# IGBT2020.net
KiCad netlist of a schematic drawn in Altium Designer
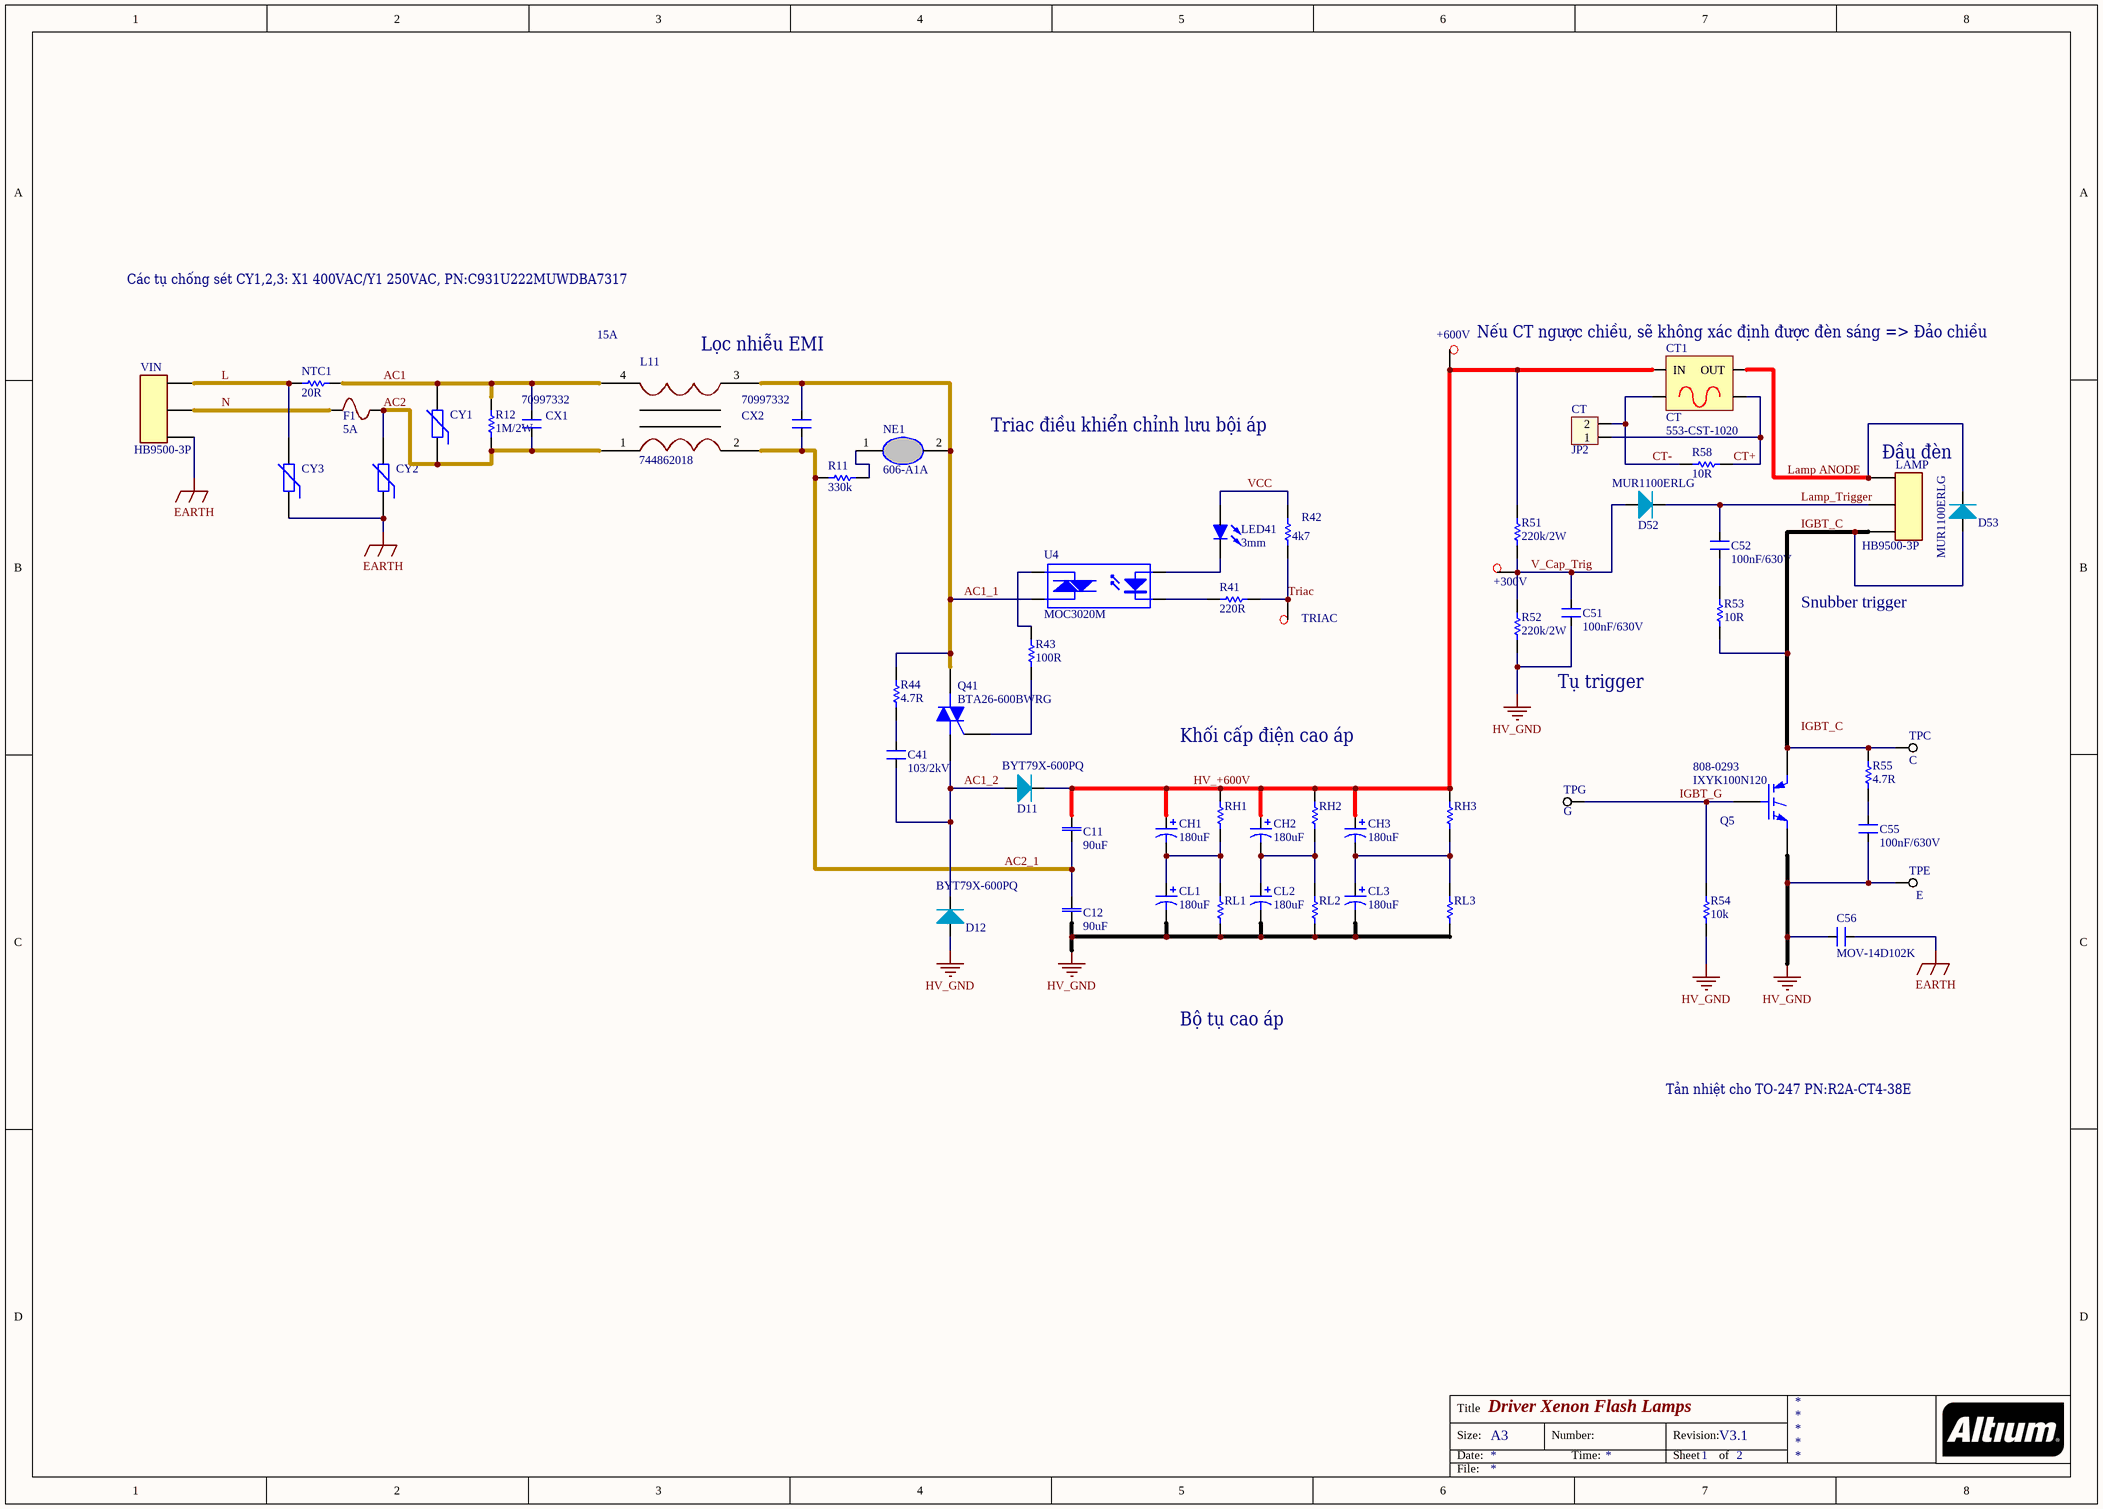
[diagram p0: IGBT2020.SchDoc]

(export (version "E")
  (design (tool "Eeschema 10.0.6"))
  (components
    (comp (ref "+300V") (value "TP") (footprint "swatpcblib:TP2") (libsource (lib "swatpcblib") (part "TP")))
    (comp (ref "+600V") (value "TP") (footprint "swatpcblib:TP2") (libsource (lib "swatpcblib") (part "TP")))
    (comp (ref "C11")
      (value "C4AQ, Film, Metallized Polypropylene, Automotive DC Link, 90 uF, 10%, 500 V, 70C, Lead Spacing = 37.5mm")
      (footprint "PCBLibrary:Kemet 90uF 500V")
      (fields
        (field (name "MANUFACTURER") "WIMA")
        (field (name "MANUFACTURER PART NUMBER") "C4AQLBW5900A3OK")
        (field (name "CAPACITANCE") "90uF")
        (field (name "TOLERANCE") "10%")
      )
      (libsource (lib "swatpcblib") (part "CAP NP"))
    )
    (comp (ref "C12")
      (value "C4AQ, Film, Metallized Polypropylene, Automotive DC Link, 90 uF, 10%, 500 V, 70C, Lead Spacing = 37.5mm")
      (footprint "PCBLibrary:Kemet 90uF 500V")
      (fields
        (field (name "MANUFACTURER") "WIMA")
        (field (name "MANUFACTURER PART NUMBER") "C4AQLBW5900A3OK")
        (field (name "CAPACITANCE") "90uF")
        (field (name "TOLERANCE") "10%")
      )
      (libsource (lib "swatpcblib") (part "CAP NP"))
    )
    (comp (ref "C41")
      (value "103/2kV")
      (footprint "CN2-LT")
      (description "Tụ cao áp chân cắm")
      (libsource (lib "Schematic Library") (part "CN"))
    )
    (comp (ref "C51")
      (value "100nF/630V")
      (footprint "X2 CAP")
      (fields
        (field (name "MANUFACTURER") "TDK EPCOS")
        (field (name "MANUFACTURER PART NUMBER") "B32652-A6104-J")
        (field (name "TOLERANCE") "5%")
      )
      (libsource (lib "Schematic Library") (part "CN"))
    )
    (comp (ref "C52")
      (value "100nF/630V")
      (footprint "X2 CAP")
      (fields
        (field (name "MANUFACTURER") "TDK EPCOS")
        (field (name "MANUFACTURER PART NUMBER") "B32652-A6104-J")
        (field (name "TOLERANCE") "5%")
      )
      (libsource (lib "Schematic Library") (part "CN"))
    )
    (comp (ref "C55")
      (value "100nF/630V")
      (footprint "X2 CAP")
      (fields
        (field (name "MANUFACTURER") "TDK EPCOS")
        (field (name "MANUFACTURER PART NUMBER") "B32652-A6104-J")
        (field (name "TOLERANCE") "5%")
      )
      (libsource (lib "Schematic Library") (part "CN"))
    )
    (comp (ref "C56")
      (value "MOV-14D102K")
      (footprint "MOV")
      (description "Tụ cao áp chân cắm")
      (fields (field (name "MANUFACTURER") "Bourns") (field (name "TOLERANCE") "10%"))
      (libsource (lib "Schematic Library") (part "CN"))
    )
    (comp (ref "CH1")
      (value "180uF")
      (footprint "CAP 25x50")
      (fields
        (field (name "MANUFACTURER") "Wurth Electronics")
        (field (name "MANUFACTURER PART NUMBER") "861141483005")
        (field (name "TOLERANCE") "20%")
      )
      (libsource (lib "Schematic Library") (part "CP"))
    )
    (comp (ref "CH2")
      (value "180uF")
      (footprint "CAP 25x50")
      (fields
        (field (name "MANUFACTURER") "Wurth Electronics")
        (field (name "MANUFACTURER PART NUMBER") "861141483005")
        (field (name "TOLERANCE") "20%")
      )
      (libsource (lib "Schematic Library") (part "CP"))
    )
    (comp (ref "CH3")
      (value "180uF")
      (footprint "CAP 25x50")
      (fields
        (field (name "MANUFACTURER") "Wurth Electronics")
        (field (name "MANUFACTURER PART NUMBER") "861141483005")
        (field (name "TOLERANCE") "20%")
      )
      (libsource (lib "Schematic Library") (part "CP"))
    )
    (comp (ref "CL1")
      (value "180uF")
      (footprint "CAP 25x50")
      (fields
        (field (name "MANUFACTURER") "Wurth Electronics")
        (field (name "MANUFACTURER PART NUMBER") "861141483005")
        (field (name "TOLERANCE") "20%")
      )
      (libsource (lib "Schematic Library") (part "CP"))
    )
    (comp (ref "CL2")
      (value "180uF")
      (footprint "CAP 25x50")
      (fields
        (field (name "MANUFACTURER") "Wurth Electronics")
        (field (name "MANUFACTURER PART NUMBER") "861141483005")
        (field (name "TOLERANCE") "20%")
      )
      (libsource (lib "Schematic Library") (part "CP"))
    )
    (comp (ref "CL3")
      (value "180uF")
      (footprint "CAP 25x50")
      (fields
        (field (name "MANUFACTURER") "Wurth Electronics")
        (field (name "MANUFACTURER PART NUMBER") "861141483005")
        (field (name "TOLERANCE") "20%")
      )
      (libsource (lib "Schematic Library") (part "CP"))
    )
    (comp (ref "CT")
      (value "JP2")
      (footprint "heromap:CON2")
      (description "Connector 2")
      (libsource (lib "heromap") (part "Con2"))
    )
    (comp (ref "CT1")
      (value "CT")
      (footprint "PCBComponent_1")
      (description "Biến dòng cách ly 20A/20mA")
      (fields
        (field (name "SUPPLIER PART NUMBER 1") "553-CST-1020")
        (field (name "MANUFACTURER") "Triad Magnetics")
        (field (name "MANUFACTURER PART NUMBER") "CST-1020")
      )
      (libsource (lib "Tuan") (part "CT"))
    )
    (comp (ref "CX1")
      (value "Tụ lọc nhiễu X2 chân cắm220nF70997332")
      (footprint "X2 CAP")
      (description "Tụ lọc nhiễu X2 chân cắm")
      (fields
        (field (name "SPN1") "70997332")
        (field (name "MANUFACTURER") "Wurth Electronics")
        (field (name "MANUFACTURER PART NUMBER") "890324024002CS")
      )
      (libsource (lib "Schematic Library") (part "CN"))
    )
    (comp (ref "CX2")
      (value "Tụ lọc nhiễu X2 chân cắm220nF70997332")
      (footprint "X2 CAP")
      (description "Tụ lọc nhiễu X2 chân cắm")
      (fields
        (field (name "SPN1") "70997332")
        (field (name "MANUFACTURER") "Wurth Electronics")
        (field (name "MANUFACTURER PART NUMBER") "890324024002CS")
      )
      (libsource (lib "Schematic Library") (part "CN"))
    )
    (comp (ref "CY1")
      (value "Varistor chân cắmC931U222MUWDBA7317")
      (footprint "MOV")
      (description "Ceramic Disc Capacitors 250volts 2200pF 20% Y5U")
      (fields (field (name "MANUFACTURER") "KEMET") (field (name "MPN") "C931U222MUWDBA7317"))
      (libsource (lib "Schematic Library") (part "Varistor"))
    )
    (comp (ref "CY2")
      (value "Varistor chân cắmC931U222MUWDBA7317")
      (footprint "MOV")
      (description "Ceramic Disc Capacitors 250volts 2200pF 20% Y5U")
      (fields (field (name "MANUFACTURER") "KEMET") (field (name "MPN") "C931U222MUWDBA7317"))
      (libsource (lib "Schematic Library") (part "Varistor"))
    )
    (comp (ref "CY3")
      (value "Varistor chân cắmC931U222MUWDBA7317")
      (footprint "MOV")
      (description "Ceramic Disc Capacitors 250volts 2200pF 20% Y5U")
      (fields (field (name "MANUFACTURER") "KEMET") (field (name "MPN") "C931U222MUWDBA7317"))
      (libsource (lib "Schematic Library") (part "Varistor"))
    )
    (comp (ref "D11")
      (value "Đi ốt cắmBYT79X-600PQ")
      (footprint "swatpcblib:TO-220F")
      (fields
        (field (name "SUPPLIER PART NUMBER 1") "BYT79X-600PQ")
        (field (name "MANUFACTURER") "WeEn Semiconductors")
        (field (name "MPN") "BYT79X-600PQ")
      )
      (libsource (lib "swatpcblib") (part "Diode"))
    )
    (comp (ref "D12")
      (value "Đi ốt cắmBYT79X-600PQ")
      (footprint "swatpcblib:TO-220F")
      (fields
        (field (name "SUPPLIER PART NUMBER 1") "BYT79X-600PQ")
        (field (name "MANUFACTURER") "WeEn Semiconductors")
        (field (name "MPN") "BYT79X-600PQ")
      )
      (libsource (lib "swatpcblib") (part "Diode"))
    )
    (comp (ref "D52")
      (value "Đi ốt cắmMUR1100ERLG")
      (footprint "swatpcblib:DO-41")
      (description "DIODE GEN PURP 1KV 1A AXIAL")
      (fields (field (name "MANUFACTURER") "ON Semiconductor") (field (name "VL1") "MUR1100ERLG"))
      (libsource (lib "swatpcblib") (part "Diode"))
    )
    (comp (ref "D53")
      (value "Đi ốt cắmMUR1100ERLG")
      (footprint "swatpcblib:DO-41")
      (description "DIODE GEN PURP 1KV 1A AXIAL")
      (fields (field (name "MANUFACTURER") "ON Semiconductor") (field (name "VL1") "MUR1100ERLG"))
      (libsource (lib "swatpcblib") (part "Diode"))
    )
    (comp (ref "F1")
      (value "5A")
      (footprint "Fuse")
      (description "Cầu chì ống thủy tinh")
      (fields (field (name "Comment") "Cầu chì ống thủy tinh5A"))
      (libsource (lib "Schematic Library") (part "Fuse"))
    )
    (comp (ref "L11")
      (value "744862018")
      (footprint "swatpcblib:Choke 5A")
      (description "Cuộn cảm lọc nguồn đầu vào")
      (fields
        (field (name "MANUFACTURER") "Wurth Electronics")
        (field (name "TOLERANCE") "50%")
        (field (name "MAX CURRENT RATING") "15A")
      )
      (libsource (lib "Schematic Library") (part "Choke"))
    )
    (comp (ref "LAMP")
      (value "HB9500-3P")
      (footprint "HB9500-3P")
      (description "Pitch：9.5mm；Poles：3P；Rated Voltage/Current：300V/25A")
      (fields (field (name "Comment") "Giắc nguồn 3 chân. 9.5mm :HB9500-3P"))
      (libsource (lib "") (part "HEADER 3_1"))
    )
    (comp (ref "LED41")
      (value "3mm")
      (footprint "LED 3mm")
      (description "Led vàng chân cắm")
      (libsource (lib "Schematic Library") (part "LED 3mm"))
    )
    (comp (ref "NE1")
      (value "606-A1A")
      (footprint "NE2")
      (description "T2 WIRE TERMINAL NEON (NE-2)")
      (fields (field (name "MANUFACTURER") "VCC CHML") (field (name "MANUFACTURER PART NUMBER") "A1A"))
      (libsource (lib "Schematic Library") (part "NE"))
    )
    (comp (ref "NTC1")
      (value "20R")
      (footprint "PCBLibrary:TO-126")
      (description "NTC")
      (fields
        (field (name "MANUFACTURER") "Bourns")
        (field (name "MANUFACTURER PART NUMBER") "PWR221T-30-R100F")
      )
      (libsource (lib "Schematic Library") (part "Resistor"))
    )
    (comp (ref "Q5")
      (value "IXYK100N120")
      (footprint "TO247+LageHeatsink")
      (description "IGBT 1200V 188A 1150W TO264")
      (fields
        (field (name "SUPPLIER PART NUMBER 1") "808-0293")
        (field (name "MANUFACTURER") "IXYS")
        (field (name "MANUFACTURER PART NUMBER") "IXYK100N120C3")
      )
      (libsource (lib "Schematic Library") (part "IGBT"))
    )
    (comp (ref "Q41")
      (value "BTA26-600BWRG")
      (footprint "TOP3")
      (description "TRIAC, 25A, 600V, TOP-3")
      (fields (field (name "MANUFACTURER") "STMicroelectronics"))
      (libsource (lib "Schematic Library") (part "BTA26-600"))
    )
    (comp (ref "R11")
      (value "330k")
      (footprint "RES-1/4W")
      (description "Trở cắm 1/4W")
      (libsource (lib "Schematic Library") (part "Resistor"))
    )
    (comp (ref "R12")
      (value "1M/2W")
      (footprint "RES-3W")
      (description "Trở cắm 2W")
      (libsource (lib "Schematic Library") (part "Resistor"))
    )
    (comp (ref "R41")
      (value "220R")
      (footprint "RES-SMD-1206")
      (description "Trở dán SMD 1206")
      (libsource (lib "Schematic Library") (part "Resistor"))
    )
    (comp (ref "R42")
      (value "4k7")
      (footprint "RES-SMD-1206")
      (description "Trở dán SMD 1206")
      (libsource (lib "Schematic Library") (part "Resistor"))
    )
    (comp (ref "R43")
      (value "100R")
      (footprint "RES-1W")
      (description "Trở cắm 1W")
      (libsource (lib "Schematic Library") (part "Resistor"))
    )
    (comp (ref "R44")
      (value "4.7R")
      (footprint "heromap:R1/4WD")
      (description "Trở cắm 2W")
      (libsource (lib "Schematic Library") (part "Resistor"))
    )
    (comp (ref "R51")
      (value "220k/2W")
      (footprint "RES-3W")
      (description "Trở cắm 2W")
      (libsource (lib "Schematic Library") (part "Resistor"))
    )
    (comp (ref "R52")
      (value "220k/2W")
      (footprint "RES-3W")
      (description "Trở cắm 2W")
      (libsource (lib "Schematic Library") (part "Resistor"))
    )
    (comp (ref "R53")
      (value "10R")
      (footprint "heromap:R1/4WD")
      (description "Trở cắm 2W")
      (libsource (lib "Schematic Library") (part "Resistor"))
    )
    (comp (ref "R54")
      (value "10k")
      (footprint "PCBLibrary:RES-1/4W")
      (description "Resistor")
      (fields (field (name "Comment") "Điện trở cắm 1/4W10k"))
      (libsource (lib "swatpcblib") (part "Res"))
    )
    (comp (ref "R55")
      (value "4.7R")
      (footprint "heromap:R1/4WD")
      (description "Trở cắm 2W")
      (libsource (lib "Schematic Library") (part "Resistor"))
    )
    (comp (ref "R58")
      (value "10R")
      (footprint "heromap:R1/4WD")
      (description "Trở cắm 2W")
      (libsource (lib "Schematic Library") (part "Resistor"))
    )
    (comp (ref "RH1")
      (value "Trở cắm 1W330k/1W")
      (footprint "RES-1W")
      (description "Trở cắm 2W")
      (libsource (lib "Schematic Library") (part "Resistor"))
    )
    (comp (ref "RH2")
      (value "Trở cắm 1W330k/1W")
      (footprint "RES-1W")
      (description "Trở cắm 2W")
      (libsource (lib "Schematic Library") (part "Resistor"))
    )
    (comp (ref "RH3")
      (value "Trở cắm 1W330k/1W")
      (footprint "RES-1W")
      (description "Trở cắm 2W")
      (libsource (lib "Schematic Library") (part "Resistor"))
    )
    (comp (ref "RL1")
      (value "Trở cắm 1W330k/1W")
      (footprint "RES-1W")
      (description "Trở cắm 2W")
      (libsource (lib "Schematic Library") (part "Resistor"))
    )
    (comp (ref "RL2")
      (value "Trở cắm 1W330k/1W")
      (footprint "RES-1W")
      (description "Trở cắm 2W")
      (libsource (lib "Schematic Library") (part "Resistor"))
    )
    (comp (ref "RL3")
      (value "Trở cắm 1W330k/1W")
      (footprint "RES-1W")
      (description "Trở cắm 2W")
      (libsource (lib "Schematic Library") (part "Resistor"))
    )
    (comp (ref "TPC")
      (value "C")
      (footprint "TP")
      (description "Testpoint C")
      (libsource (lib "Schematic Library") (part "Test Point"))
    )
    (comp (ref "TPE")
      (value "E")
      (footprint "TP")
      (description "Testpoint E")
      (libsource (lib "Schematic Library") (part "Test Point"))
    )
    (comp (ref "TPG")
      (value "G")
      (footprint "TP")
      (description "Testpoint G")
      (libsource (lib "Schematic Library") (part "Test Point"))
    )
    (comp (ref "TRIAC") (value "TP") (footprint "swatpcblib:TP2") (libsource (lib "swatpcblib") (part "TP")))
    (comp (ref "U4")
      (value "MOC3020M")
      (footprint "DIP6/W0.3")
      (description "OPTOISOLATOR 4.17KV TRIAC 6DIP")
      (fields
        (field (name "MANUFACTURER") "ON Semiconductor / Fairchild")
        (field (name "MANUFACTURER PART NUMBER") "MOC3020-M")
      )
      (libsource (lib "Schematic Library") (part "MOC"))
    )
    (comp (ref "VIN")
      (value "HB9500-3P")
      (footprint "HB9500-3P")
      (description "Pitch：9.5mm；Poles：3P；Rated Voltage/Current：300V/25A")
      (fields (field (name "Comment") "Giắc nguồn 3 chân. 9.5mm :HB9500-3P"))
      (libsource (lib "Schematic Library") (part "HEADER 3"))
    )
  )
  (nets
    (net (code "1") (name "/AC1") (class "Default")
      (node (ref "CX1") (pin "2") (pinfunction "2_2") (pintype "passive"))
      (node (ref "CY1") (pin "2") (pinfunction "2_2") (pintype "passive"))
      (node (ref "L11") (pin "4") (pinfunction "4_4") (pintype "passive"))
      (node (ref "NTC1") (pin "2") (pinfunction "2_2") (pintype "passive"))
      (node (ref "R12") (pin "2") (pinfunction "2_2") (pintype "passive"))
    )
    (net (code "2") (name "/AC1_1") (class "Default")
      (node (ref "CX2") (pin "2") (pinfunction "2_2") (pintype "passive"))
      (node (ref "L11") (pin "3") (pinfunction "3_3") (pintype "passive"))
      (node (ref "NE1") (pin "2") (pinfunction "2_2") (pintype "passive"))
      (node (ref "Q41") (pin "2") (pinfunction "M2_2") (pintype "passive"))
      (node (ref "R44") (pin "2") (pinfunction "2_2") (pintype "passive"))
      (node (ref "U4") (pin "4") (pinfunction "Main_term_4") (pintype "passive"))
    )
    (net (code "3") (name "/AC1_2") (class "Default")
      (node (ref "C41") (pin "1") (pinfunction "1_1") (pintype "passive"))
      (node (ref "D11") (pin "A") (pinfunction "A_A") (pintype "passive"))
      (node (ref "D12") (pin "K") (pinfunction "K_K") (pintype "passive"))
      (node (ref "Q41") (pin "1") (pinfunction "M1_1") (pintype "passive"))
    )
    (net (code "4") (name "/AC2") (class "Default")
      (node (ref "CX1") (pin "1") (pinfunction "1_1") (pintype "passive"))
      (node (ref "CY1") (pin "1") (pinfunction "1_1") (pintype "passive"))
      (node (ref "CY2") (pin "2") (pinfunction "2_2") (pintype "passive"))
      (node (ref "F1") (pin "2") (pinfunction "2_2") (pintype "passive"))
      (node (ref "L11") (pin "1") (pinfunction "1_1") (pintype "passive"))
      (node (ref "R12") (pin "1") (pinfunction "1_1") (pintype "passive"))
    )
    (net (code "5") (name "/AC2_1") (class "Default")
      (node (ref "C11") (pin "1") (pinfunction "1_1") (pintype "passive"))
      (node (ref "C12") (pin "2") (pinfunction "2_2") (pintype "passive"))
      (node (ref "CX2") (pin "1") (pinfunction "1_1") (pintype "passive"))
      (node (ref "L11") (pin "2") (pinfunction "2_2") (pintype "passive"))
      (node (ref "R11") (pin "1") (pinfunction "1_1") (pintype "passive"))
    )
    (net (code "6") (name "/CT+") (class "Default")
      (node (ref "CT") (pin "1") (pinfunction "1_1") (pintype "passive"))
      (node (ref "CT1") (pin "2") (pinfunction "CT_2") (pintype "passive"))
      (node (ref "R58") (pin "1") (pinfunction "1_1") (pintype "passive"))
    )
    (net (code "7") (name "/CT-") (class "Default")
      (node (ref "CT") (pin "2") (pinfunction "2_2") (pintype "passive"))
      (node (ref "CT1") (pin "1") (pinfunction "CT_1") (pintype "passive"))
      (node (ref "R58") (pin "2") (pinfunction "2_2") (pintype "passive"))
    )
    (net (code "8") (name "/HV_+600V") (class "Default")
      (node (ref "+600V") (pin "1") (pinfunction "1_1") (pintype "passive"))
      (node (ref "C11") (pin "2") (pinfunction "2_2") (pintype "passive"))
      (node (ref "CH1") (pin "1") (pinfunction "1_1") (pintype "passive"))
      (node (ref "CH2") (pin "1") (pinfunction "1_1") (pintype "passive"))
      (node (ref "CH3") (pin "1") (pinfunction "1_1") (pintype "passive"))
      (node (ref "CT1") (pin "4") (pinfunction "IN_4") (pintype "passive"))
      (node (ref "D11") (pin "K") (pinfunction "K_K") (pintype "passive"))
      (node (ref "R51") (pin "2") (pinfunction "2_2") (pintype "passive"))
      (node (ref "RH1") (pin "2") (pinfunction "2_2") (pintype "passive"))
      (node (ref "RH2") (pin "2") (pinfunction "2_2") (pintype "passive"))
      (node (ref "RH3") (pin "2") (pinfunction "2_2") (pintype "passive"))
    )
    (net (code "9") (name "/IGBT_C") (class "Default")
      (node (ref "D53") (pin "A") (pinfunction "A_A") (pintype "passive"))
      (node (ref "LAMP") (pin "3") (pinfunction "3_3") (pintype "passive"))
      (node (ref "Q5") (pin "2") (pinfunction "C_2") (pintype "passive"))
      (node (ref "R53") (pin "1") (pinfunction "1_1") (pintype "passive"))
      (node (ref "R55") (pin "2") (pinfunction "2_2") (pintype "passive"))
      (node (ref "TPC") (pin "1") (pintype "passive"))
    )
    (net (code "10") (name "/IGBT_G") (class "Default")
      (node (ref "Q5") (pin "1") (pinfunction "G_1") (pintype "passive"))
      (node (ref "R54") (pin "2") (pinfunction "2_2") (pintype "passive"))
      (node (ref "TPG") (pin "1") (pintype "passive"))
    )
    (net (code "11") (name "/L") (class "Default")
      (node (ref "CY3") (pin "2") (pinfunction "2_2") (pintype "passive"))
      (node (ref "NTC1") (pin "1") (pinfunction "1_1") (pintype "passive"))
      (node (ref "VIN") (pin "2") (pinfunction "2_2") (pintype "passive"))
    )
    (net (code "12") (name "/Lamp ANODE") (class "Default")
      (node (ref "CT1") (pin "3") (pinfunction "OUT_3") (pintype "passive"))
      (node (ref "D53") (pin "K") (pinfunction "K_K") (pintype "passive"))
      (node (ref "LAMP") (pin "2") (pinfunction "2_2") (pintype "passive"))
    )
    (net (code "13") (name "/Lamp_Trigger") (class "Default")
      (node (ref "C52") (pin "2") (pinfunction "2_2") (pintype "passive"))
      (node (ref "D52") (pin "K") (pinfunction "K_K") (pintype "passive"))
      (node (ref "LAMP") (pin "1") (pinfunction "1_1") (pintype "passive"))
    )
    (net (code "14") (name "/N") (class "Default")
      (node (ref "F1") (pin "1") (pinfunction "1_1") (pintype "passive"))
      (node (ref "VIN") (pin "1") (pinfunction "1_1") (pintype "passive"))
    )
    (net (code "15") (name "/Triac") (class "Default")
      (node (ref "R41") (pin "1") (pinfunction "1_1") (pintype "passive"))
      (node (ref "R42") (pin "1") (pinfunction "1_1") (pintype "passive"))
      (node (ref "TRIAC") (pin "1") (pinfunction "1_1") (pintype "passive"))
    )
    (net (code "16") (name "/VCC") (class "Default")
      (node (ref "LED41") (pin "1") (pinfunction "1_1") (pintype "passive"))
      (node (ref "R42") (pin "2") (pinfunction "2_2") (pintype "passive"))
    )
    (net (code "17") (name "/V_Cap_Trig") (class "Default")
      (node (ref "+300V") (pin "1") (pinfunction "1_1") (pintype "passive"))
      (node (ref "C51") (pin "2") (pinfunction "2_2") (pintype "passive"))
      (node (ref "D52") (pin "A") (pinfunction "A_A") (pintype "passive"))
      (node (ref "R51") (pin "1") (pinfunction "1_1") (pintype "passive"))
      (node (ref "R52") (pin "2") (pinfunction "2_2") (pintype "passive"))
    )
    (net (code "18") (name "EARTH") (class "Default")
      (node (ref "C56") (pin "1") (pinfunction "1_1") (pintype "passive"))
      (node (ref "CY2") (pin "1") (pinfunction "1_1") (pintype "passive"))
      (node (ref "CY3") (pin "1") (pinfunction "1_1") (pintype "passive"))
      (node (ref "VIN") (pin "3") (pinfunction "3_3") (pintype "passive"))
    )
    (net (code "19") (name "HV_GND") (class "Default")
      (node (ref "C12") (pin "1") (pinfunction "1_1") (pintype "passive"))
      (node (ref "C51") (pin "1") (pinfunction "1_1") (pintype "passive"))
      (node (ref "C55") (pin "1") (pinfunction "1_1") (pintype "passive"))
      (node (ref "C56") (pin "2") (pinfunction "2_2") (pintype "passive"))
      (node (ref "CL1") (pin "2") (pinfunction "2_2") (pintype "passive"))
      (node (ref "CL2") (pin "2") (pinfunction "2_2") (pintype "passive"))
      (node (ref "CL3") (pin "2") (pinfunction "2_2") (pintype "passive"))
      (node (ref "D12") (pin "A") (pinfunction "A_A") (pintype "passive"))
      (node (ref "Q5") (pin "3") (pinfunction "E_3") (pintype "passive"))
      (node (ref "R52") (pin "1") (pinfunction "1_1") (pintype "passive"))
      (node (ref "R54") (pin "1") (pinfunction "1_1") (pintype "passive"))
      (node (ref "RL1") (pin "1") (pinfunction "1_1") (pintype "passive"))
      (node (ref "RL2") (pin "1") (pinfunction "1_1") (pintype "passive"))
      (node (ref "RL3") (pin "1") (pinfunction "1_1") (pintype "passive"))
      (node (ref "TPE") (pin "1") (pintype "passive"))
    )
    (net (code "20") (name "Net-(C41-Pad2)") (class "Default")
      (node (ref "C41") (pin "2") (pinfunction "2_2") (pintype "passive"))
      (node (ref "R44") (pin "1") (pinfunction "1_1") (pintype "passive"))
    )
    (net (code "21") (name "Net-(C52-Pad1)") (class "Default")
      (node (ref "C52") (pin "1") (pinfunction "1_1") (pintype "passive"))
      (node (ref "R53") (pin "2") (pinfunction "2_2") (pintype "passive"))
    )
    (net (code "22") (name "Net-(C55-Pad2)") (class "Default")
      (node (ref "C55") (pin "2") (pinfunction "2_2") (pintype "passive"))
      (node (ref "R55") (pin "1") (pinfunction "1_1") (pintype "passive"))
    )
    (net (code "23") (name "Net-(CH1-Pad2)") (class "Default")
      (node (ref "CH1") (pin "2") (pinfunction "2_2") (pintype "passive"))
      (node (ref "CL1") (pin "1") (pinfunction "1_1") (pintype "passive"))
      (node (ref "RH1") (pin "1") (pinfunction "1_1") (pintype "passive"))
      (node (ref "RL1") (pin "2") (pinfunction "2_2") (pintype "passive"))
    )
    (net (code "24") (name "Net-(CH2-Pad2)") (class "Default")
      (node (ref "CH2") (pin "2") (pinfunction "2_2") (pintype "passive"))
      (node (ref "CL2") (pin "1") (pinfunction "1_1") (pintype "passive"))
      (node (ref "RH2") (pin "1") (pinfunction "1_1") (pintype "passive"))
      (node (ref "RL2") (pin "2") (pinfunction "2_2") (pintype "passive"))
    )
    (net (code "25") (name "Net-(CH3-Pad2)") (class "Default")
      (node (ref "CH3") (pin "2") (pinfunction "2_2") (pintype "passive"))
      (node (ref "CL3") (pin "1") (pinfunction "1_1") (pintype "passive"))
      (node (ref "RH3") (pin "1") (pinfunction "1_1") (pintype "passive"))
      (node (ref "RL3") (pin "2") (pinfunction "2_2") (pintype "passive"))
    )
    (net (code "26") (name "Net-(NE1-Pad1)") (class "Default")
      (node (ref "NE1") (pin "1") (pinfunction "1_1") (pintype "passive"))
      (node (ref "R11") (pin "2") (pinfunction "2_2") (pintype "passive"))
    )
    (net (code "27") (name "Net-(Q41-G)") (class "Default")
      (node (ref "Q41") (pin "3") (pinfunction "G_3") (pintype "passive"))
      (node (ref "R43") (pin "1") (pinfunction "1_1") (pintype "passive"))
    )
    (net (code "28") (name "Net-(U4-A)") (class "Default")
      (node (ref "LED41") (pin "2") (pinfunction "2_2") (pintype "passive"))
      (node (ref "U4") (pin "1") (pinfunction "A_1") (pintype "passive"))
    )
    (net (code "29") (name "Net-(U4-K)") (class "Default")
      (node (ref "R41") (pin "2") (pinfunction "2_2") (pintype "passive"))
      (node (ref "U4") (pin "2") (pinfunction "K_2") (pintype "passive"))
    )
    (net (code "30") (name "Net-(U4-Main_tern)") (class "Default")
      (node (ref "R43") (pin "2") (pinfunction "2_2") (pintype "passive"))
      (node (ref "U4") (pin "6") (pinfunction "Main_tern_6") (pintype "passive"))
    )
  )
)
